# mdriver_v2.net
KiCad netlist of a schematic drawn in EAGLE
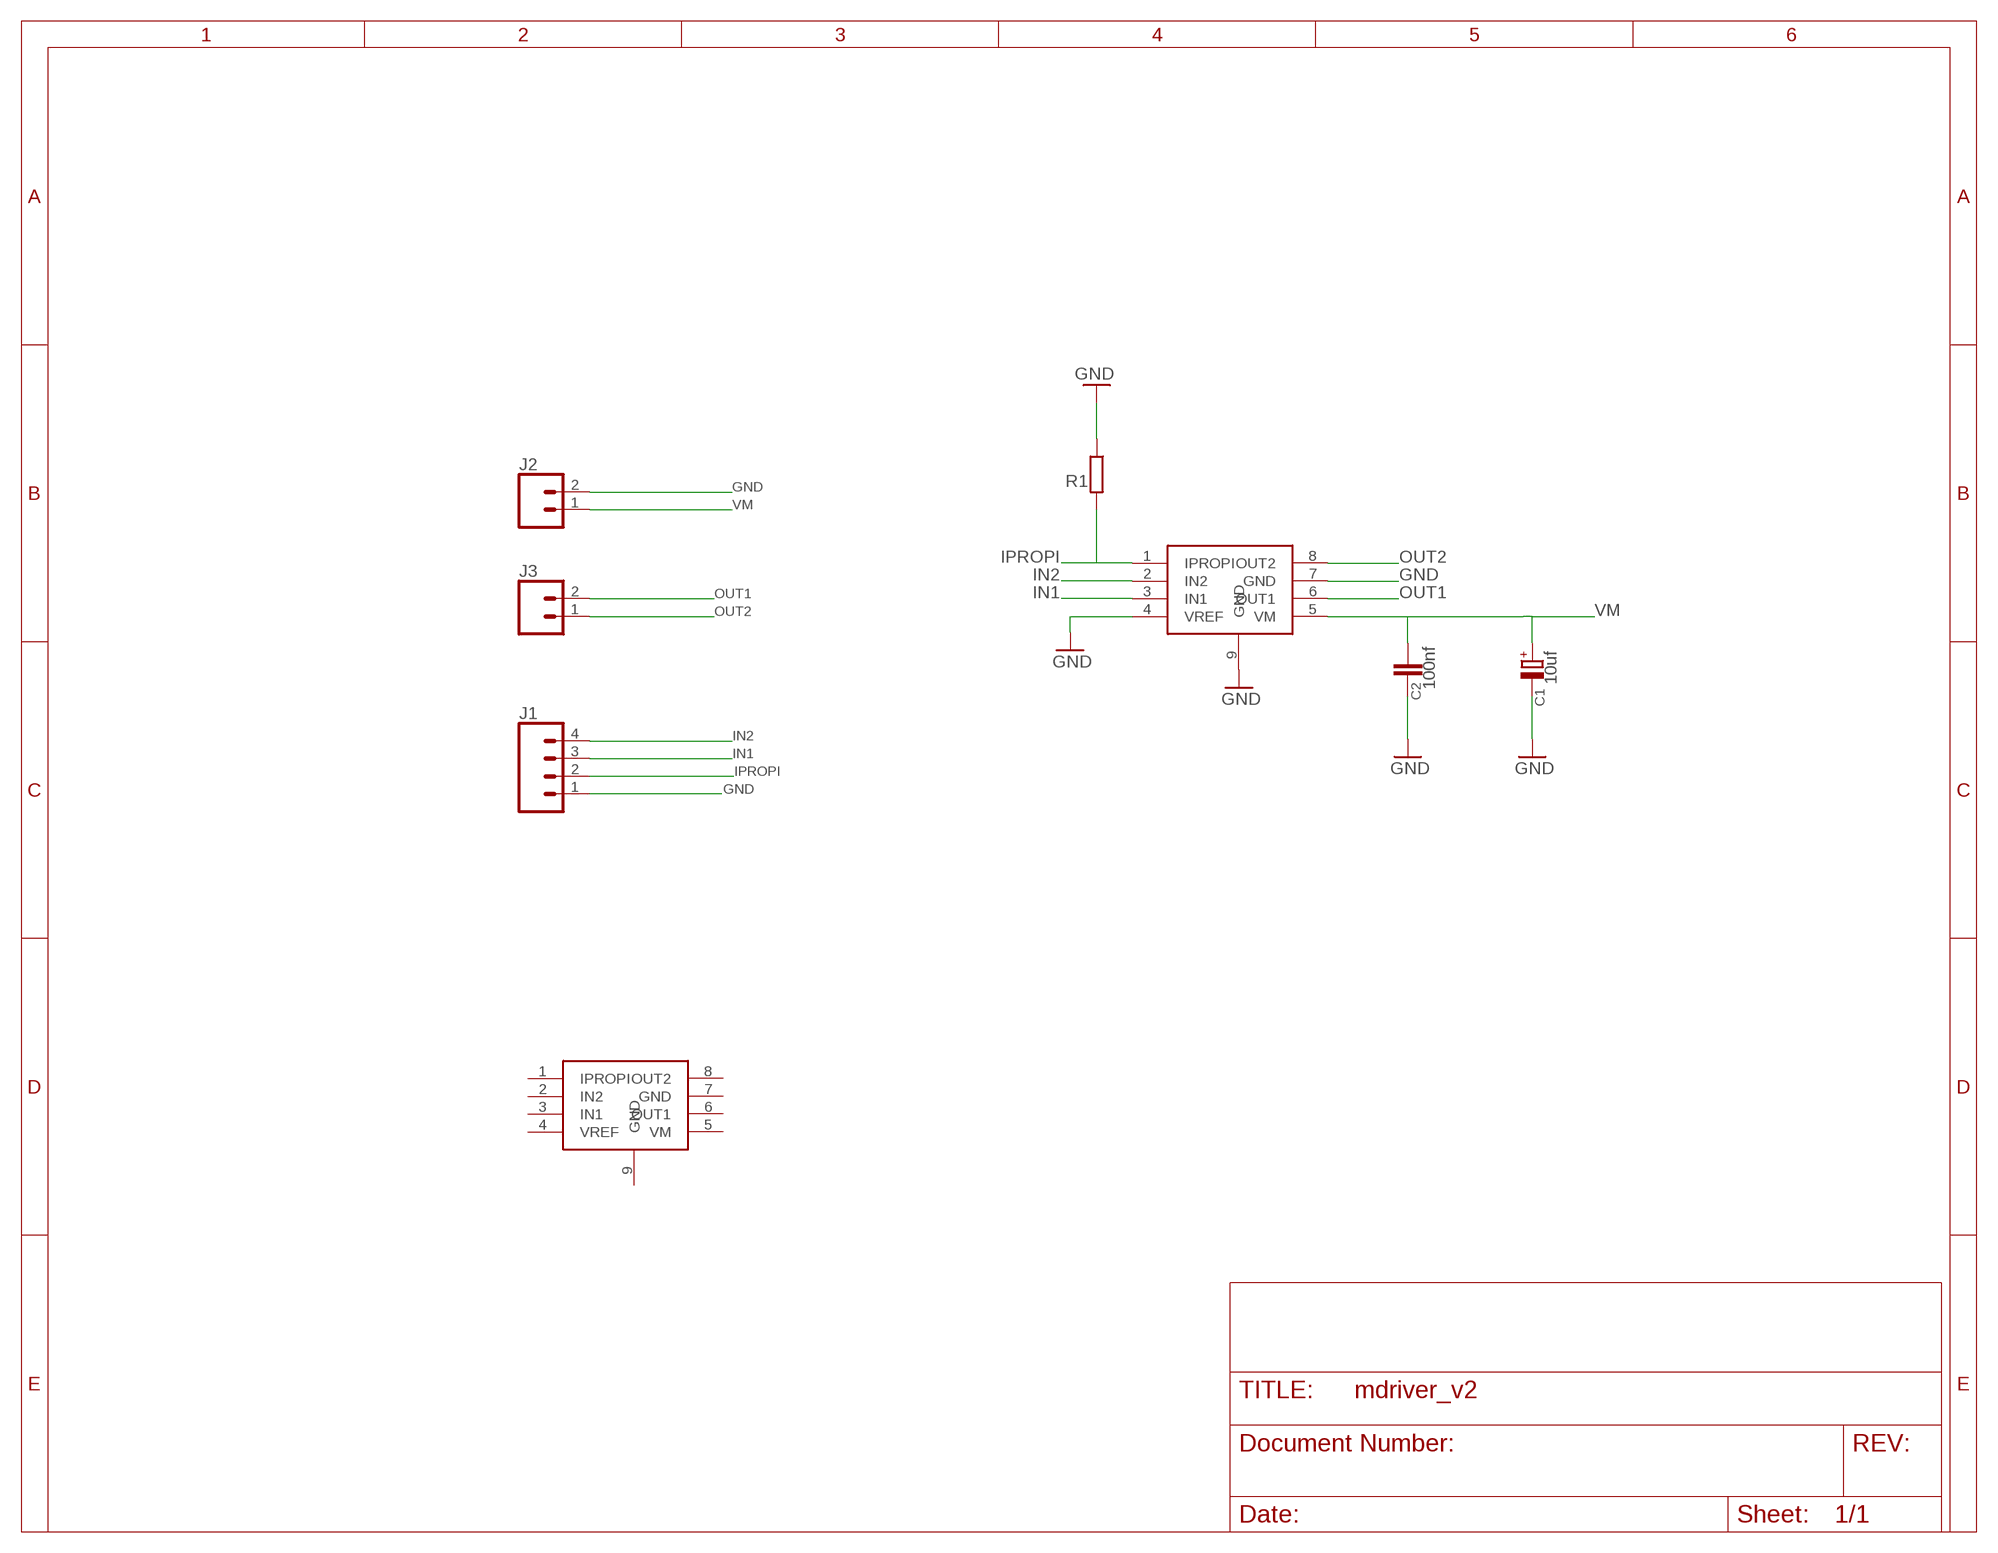
[diagram p0: schematic, sheet 1]

(export (version "E")
  (design (tool "Eeschema 10.0.6"))
  (components
    (comp (ref "C1")
      (value "10uf")
      (footprint "eagle-import:E2,5-6E")
      (libsource (lib "eagle-import") (part "CPOL-EUE2,5-6E"))
    )
    (comp (ref "C2")
      (value "100nf")
      (footprint "eagle-import:C025-025X050")
      (libsource (lib "eagle-import") (part "C-EU025-025X050"))
    )
    (comp (ref "J1")
      (value "CONN_04")
      (footprint "eagle-import:1X04")
      (libsource (lib "eagle-import") (part "CONN_04"))
    )
    (comp (ref "J2")
      (value "CONN_02")
      (footprint "eagle-import:1X02")
      (libsource (lib "eagle-import") (part "CONN_02"))
    )
    (comp (ref "J3")
      (value "CONN_02")
      (footprint "eagle-import:1X02")
      (libsource (lib "eagle-import") (part "CONN_02"))
    )
    (comp (ref "R1")
      (value "SMK")
      (footprint "eagle-import:SMK")
      (libsource (lib "eagle-import") (part "SMK"))
    )
    (comp (ref "U$1")
      (value "DRV8231A")
      (footprint "eagle-import:SOIC127P580X170-9T271X340N")
      (libsource (lib "eagle-import") (part "DRV8231A"))
    )
    (comp (ref "U$2")
      (value "DRV8231A")
      (footprint "eagle-import:SOIC127P580X170-9T271X340N")
      (libsource (lib "eagle-import") (part "DRV8231A"))
    )
  )
  (nets
    (net (code "1") (name "/IN1") (class "Default")
      (node (ref "J1") (pin "3") (pinfunction "3_3") (pintype "passive"))
      (node (ref "U$1") (pin "3") (pinfunction "IN1_3") (pintype "bidirectional"))
    )
    (net (code "2") (name "/IN2") (class "Default")
      (node (ref "J1") (pin "4") (pinfunction "4_4") (pintype "passive"))
      (node (ref "U$1") (pin "2") (pinfunction "IN2_2") (pintype "bidirectional"))
    )
    (net (code "3") (name "/IPROPI") (class "Default")
      (node (ref "J1") (pin "2") (pinfunction "2_2") (pintype "passive"))
      (node (ref "R1") (pin "2") (pinfunction "2_2") (pintype "passive"))
      (node (ref "U$1") (pin "1") (pinfunction "IPROPI_1") (pintype "bidirectional"))
    )
    (net (code "4") (name "/OUT1") (class "Default")
      (node (ref "J3") (pin "2") (pinfunction "2_2") (pintype "passive"))
      (node (ref "U$1") (pin "6") (pinfunction "OUT1_6") (pintype "bidirectional"))
    )
    (net (code "5") (name "/OUT2") (class "Default")
      (node (ref "J3") (pin "1") (pinfunction "1_1") (pintype "passive"))
      (node (ref "U$1") (pin "8") (pinfunction "OUT2_8") (pintype "bidirectional"))
    )
    (net (code "6") (name "/VM") (class "Default")
      (node (ref "C1") (pin "+") (pinfunction "+_+") (pintype "passive"))
      (node (ref "C2") (pin "1") (pinfunction "1_1") (pintype "passive"))
      (node (ref "J2") (pin "1") (pinfunction "1_1") (pintype "passive"))
      (node (ref "U$1") (pin "5") (pinfunction "VM_5") (pintype "bidirectional"))
    )
    (net (code "7") (name "GND") (class "Default")
      (node (ref "C1") (pin "-") (pinfunction "-_-") (pintype "passive"))
      (node (ref "C2") (pin "2") (pinfunction "2_2") (pintype "passive"))
      (node (ref "J1") (pin "1") (pinfunction "1_1") (pintype "passive"))
      (node (ref "J2") (pin "2") (pinfunction "2_2") (pintype "passive"))
      (node (ref "R1") (pin "1") (pinfunction "1_1") (pintype "passive"))
      (node (ref "U$1") (pin "4") (pinfunction "VREF_4") (pintype "bidirectional"))
      (node (ref "U$1") (pin "7") (pinfunction "GND_7") (pintype "bidirectional"))
      (node (ref "U$1") (pin "9") (pinfunction "GND_9") (pintype "bidirectional"))
    )
    (net (code "8") (name "unconnected-(U$2-GND-Pad7)") (class "Default")
      (node (ref "U$2") (pin "7") (pinfunction "GND_7") (pintype "bidirectional"))
    )
    (net (code "9") (name "unconnected-(U$2-GND-Pad9)") (class "Default")
      (node (ref "U$2") (pin "9") (pinfunction "GND_9") (pintype "bidirectional"))
    )
    (net (code "10") (name "unconnected-(U$2-IN1-Pad3)") (class "Default")
      (node (ref "U$2") (pin "3") (pinfunction "IN1_3") (pintype "bidirectional"))
    )
    (net (code "11") (name "unconnected-(U$2-IN2-Pad2)") (class "Default")
      (node (ref "U$2") (pin "2") (pinfunction "IN2_2") (pintype "bidirectional"))
    )
    (net (code "12") (name "unconnected-(U$2-IPROPI-Pad1)") (class "Default")
      (node (ref "U$2") (pin "1") (pinfunction "IPROPI_1") (pintype "bidirectional"))
    )
    (net (code "13") (name "unconnected-(U$2-OUT1-Pad6)") (class "Default")
      (node (ref "U$2") (pin "6") (pinfunction "OUT1_6") (pintype "bidirectional"))
    )
    (net (code "14") (name "unconnected-(U$2-OUT2-Pad8)") (class "Default")
      (node (ref "U$2") (pin "8") (pinfunction "OUT2_8") (pintype "bidirectional"))
    )
    (net (code "15") (name "unconnected-(U$2-VM-Pad5)") (class "Default")
      (node (ref "U$2") (pin "5") (pinfunction "VM_5") (pintype "bidirectional"))
    )
    (net (code "16") (name "unconnected-(U$2-VREF-Pad4)") (class "Default")
      (node (ref "U$2") (pin "4") (pinfunction "VREF_4") (pintype "bidirectional"))
    )
  )
)
